# coils.net
KiCad netlist of a schematic drawn in Altium Designer
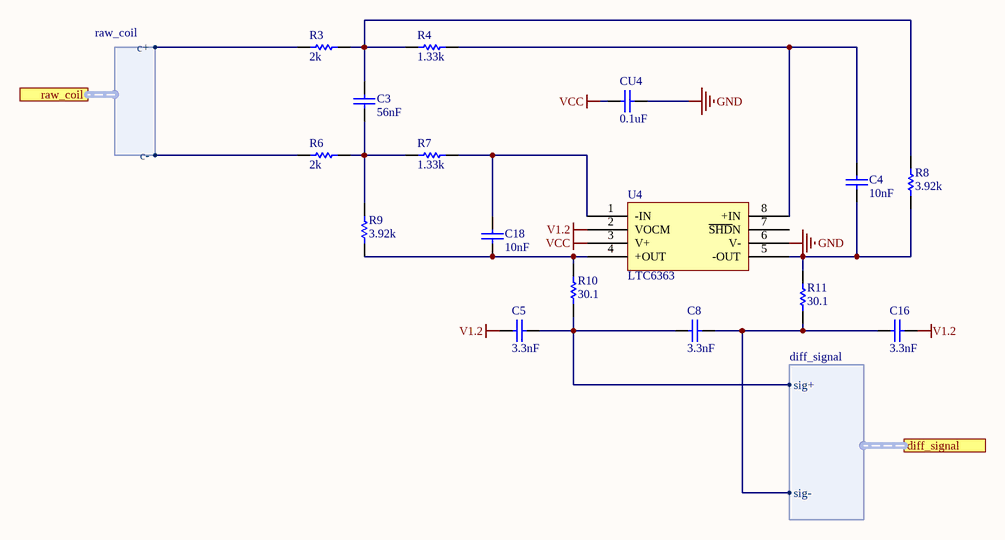
[diagram p0: coils.SchDoc]

(export (version "E")
  (design (tool "Eeschema 10.0.6"))
  (components
    (comp (ref "C3")
      (value "56nF")
      (footprint "0402")
      (description "Ceramic Capacitor (Surface Mount)")
      (fields (field (name "MANUFACTURER") "Generic Ceramic Chip Cap (TBD)") (field (name "Comment") "Cap"))
      (libsource (lib "maglib") (part "Cap"))
    )
    (comp (ref "C4")
      (value "10nF")
      (footprint "0402")
      (description "Ceramic Capacitor (Surface Mount)")
      (fields (field (name "MANUFACTURER") "Generic Ceramic Chip Cap (TBD)") (field (name "Comment") "Cap"))
      (libsource (lib "maglib") (part "Cap"))
    )
    (comp (ref "C5")
      (value "3.3nF")
      (footprint "0402")
      (description "Ceramic Capacitor (Surface Mount)")
      (fields (field (name "MANUFACTURER") "Generic Ceramic Chip Cap (TBD)") (field (name "Comment") "Cap"))
      (libsource (lib "maglib") (part "Cap"))
    )
    (comp (ref "C8")
      (value "3.3nF")
      (footprint "0402")
      (description "Ceramic Capacitor (Surface Mount)")
      (fields (field (name "MANUFACTURER") "Generic Ceramic Chip Cap (TBD)") (field (name "Comment") "Cap"))
      (libsource (lib "maglib") (part "Cap"))
    )
    (comp (ref "C16")
      (value "3.3nF")
      (footprint "0402")
      (description "Ceramic Capacitor (Surface Mount)")
      (fields (field (name "MANUFACTURER") "Generic Ceramic Chip Cap (TBD)") (field (name "Comment") "Cap"))
      (libsource (lib "maglib") (part "Cap"))
    )
    (comp (ref "C18")
      (value "10nF")
      (footprint "0402")
      (description "Ceramic Capacitor (Surface Mount)")
      (fields (field (name "MANUFACTURER") "Generic Ceramic Chip Cap (TBD)") (field (name "Comment") "Cap"))
      (libsource (lib "maglib") (part "Cap"))
    )
    (comp (ref "CU4")
      (value "0.1uF")
      (footprint "0402")
      (description "Ceramic Capacitor (Surface Mount)")
      (fields (field (name "MANUFACTURER") "Generic Ceramic Chip Cap (TBD)") (field (name "Comment") "Cap"))
      (libsource (lib "maglib") (part "Cap"))
    )
    (comp (ref "R3")
      (value "2k")
      (footprint "0402")
      (description "Chip Resistor (Surface Mount)")
      (fields (field (name "MANUFACTURER") "Generic Chip Res (TBD)") (field (name "Comment") "Res"))
      (libsource (lib "maglib") (part "Res"))
    )
    (comp (ref "R4")
      (value "1.33k")
      (footprint "0402")
      (description "Chip Resistor (Surface Mount)")
      (fields (field (name "MANUFACTURER") "Generic Chip Res (TBD)") (field (name "Comment") "Res"))
      (libsource (lib "maglib") (part "Res"))
    )
    (comp (ref "R6")
      (value "2k")
      (footprint "0402")
      (description "Chip Resistor (Surface Mount)")
      (fields (field (name "MANUFACTURER") "Generic Chip Res (TBD)") (field (name "Comment") "Res"))
      (libsource (lib "maglib") (part "Res"))
    )
    (comp (ref "R7")
      (value "1.33k")
      (footprint "0402")
      (description "Chip Resistor (Surface Mount)")
      (fields (field (name "MANUFACTURER") "Generic Chip Res (TBD)") (field (name "Comment") "Res"))
      (libsource (lib "maglib") (part "Res"))
    )
    (comp (ref "R8")
      (value "3.92k")
      (footprint "0402")
      (description "Chip Resistor (Surface Mount)")
      (fields (field (name "MANUFACTURER") "Generic Chip Res (TBD)") (field (name "Comment") "Res"))
      (libsource (lib "maglib") (part "Res"))
    )
    (comp (ref "R9")
      (value "3.92k")
      (footprint "0402")
      (description "Chip Resistor (Surface Mount)")
      (fields (field (name "MANUFACTURER") "Generic Chip Res (TBD)") (field (name "Comment") "Res"))
      (libsource (lib "maglib") (part "Res"))
    )
    (comp (ref "R10")
      (value "30.1")
      (footprint "0402")
      (description "Chip Resistor (Surface Mount)")
      (fields (field (name "MANUFACTURER") "Generic Chip Res (TBD)") (field (name "Comment") "Res"))
      (libsource (lib "maglib") (part "Res"))
    )
    (comp (ref "R11")
      (value "30.1")
      (footprint "0402")
      (description "Chip Resistor (Surface Mount)")
      (fields (field (name "MANUFACTURER") "Generic Chip Res (TBD)") (field (name "Comment") "Res"))
      (libsource (lib "maglib") (part "Res"))
    )
    (comp (ref "U4")
      (value "LTC6363")
      (footprint "TSOP65P490X110-8N - LTC6363")
      (libsource (lib "maglib") (part "LTC6363"))
    )
  )
  (nets
    (net (code "3") (name "/c+") (class "Default")
      (node (ref "R3") (pin "2") (pinfunction "2_2") (pintype "passive"))
    )
    (net (code "4") (name "/c-") (class "Default")
      (node (ref "R6") (pin "2") (pinfunction "2_2") (pintype "passive"))
    )
    (net (code "5") (name "/sig+") (class "Default")
      (node (ref "C5") (pin "1") (pinfunction "1_1") (pintype "passive"))
      (node (ref "C8") (pin "2") (pinfunction "2_2") (pintype "passive"))
      (node (ref "R10") (pin "2") (pinfunction "2_2") (pintype "passive"))
    )
    (net (code "6") (name "/sig-") (class "Default")
      (node (ref "C16") (pin "2") (pinfunction "2_2") (pintype "passive"))
      (node (ref "C8") (pin "1") (pinfunction "1_1") (pintype "passive"))
      (node (ref "R11") (pin "2") (pinfunction "2_2") (pintype "passive"))
    )
    (net (code "9") (name "GND") (class "Default")
      (node (ref "CU4") (pin "1") (pinfunction "1_1") (pintype "passive"))
      (node (ref "U4") (pin "6") (pinfunction "V-_6") (pintype "power_in"))
    )
    (net (code "10") (name "Net-(C3-Pad1)") (class "Default")
      (node (ref "C3") (pin "1") (pinfunction "1_1") (pintype "passive"))
      (node (ref "R6") (pin "1") (pinfunction "1_1") (pintype "passive"))
      (node (ref "R7") (pin "2") (pinfunction "2_2") (pintype "passive"))
      (node (ref "R9") (pin "1") (pinfunction "1_1") (pintype "passive"))
    )
    (net (code "11") (name "Net-(C3-Pad2)") (class "Default")
      (node (ref "C3") (pin "2") (pinfunction "2_2") (pintype "passive"))
      (node (ref "R3") (pin "1") (pinfunction "1_1") (pintype "passive"))
      (node (ref "R4") (pin "2") (pinfunction "2_2") (pintype "passive"))
      (node (ref "R8") (pin "1") (pinfunction "1_1") (pintype "passive"))
    )
    (net (code "12") (name "Net-(U4-+IN)") (class "Default")
      (node (ref "C4") (pin "2") (pinfunction "2_2") (pintype "passive"))
      (node (ref "R4") (pin "1") (pinfunction "1_1") (pintype "passive"))
      (node (ref "U4") (pin "8") (pinfunction "+IN_8") (pintype "passive"))
    )
    (net (code "13") (name "Net-(U4-+OUT)") (class "Default")
      (node (ref "C18") (pin "1") (pinfunction "1_1") (pintype "passive"))
      (node (ref "R10") (pin "1") (pinfunction "1_1") (pintype "passive"))
      (node (ref "R9") (pin "2") (pinfunction "2_2") (pintype "passive"))
      (node (ref "U4") (pin "4") (pinfunction "+OUT_4") (pintype "passive"))
    )
    (net (code "14") (name "Net-(U4--IN)") (class "Default")
      (node (ref "C18") (pin "2") (pinfunction "2_2") (pintype "passive"))
      (node (ref "R7") (pin "1") (pinfunction "1_1") (pintype "passive"))
      (node (ref "U4") (pin "1") (pinfunction "-IN_1") (pintype "passive"))
    )
    (net (code "15") (name "Net-(U4--OUT)") (class "Default")
      (node (ref "C4") (pin "1") (pinfunction "1_1") (pintype "passive"))
      (node (ref "R11") (pin "1") (pinfunction "1_1") (pintype "passive"))
      (node (ref "R8") (pin "2") (pinfunction "2_2") (pintype "passive"))
      (node (ref "U4") (pin "5") (pinfunction "-OUT_5") (pintype "passive"))
    )
    (net (code "16") (name "V1.2") (class "Default")
      (node (ref "C16") (pin "1") (pinfunction "1_1") (pintype "passive"))
      (node (ref "C5") (pin "2") (pinfunction "2_2") (pintype "passive"))
      (node (ref "U4") (pin "2") (pinfunction "VOCM_2") (pintype "passive"))
    )
    (net (code "17") (name "VCC") (class "Default")
      (node (ref "CU4") (pin "2") (pinfunction "2_2") (pintype "passive"))
      (node (ref "U4") (pin "3") (pinfunction "V+_3") (pintype "power_in"))
    )
    (net (code "18") (name "unconnected-(U4-~{SHD}N-Pad7)") (class "Default")
      (node (ref "U4") (pin "7") (pinfunction "~{SHD}N_7") (pintype "passive"))
    )
  )
)
